# eclaire_sub_board.net
KiCad netlist of a schematic drawn in EAGLE
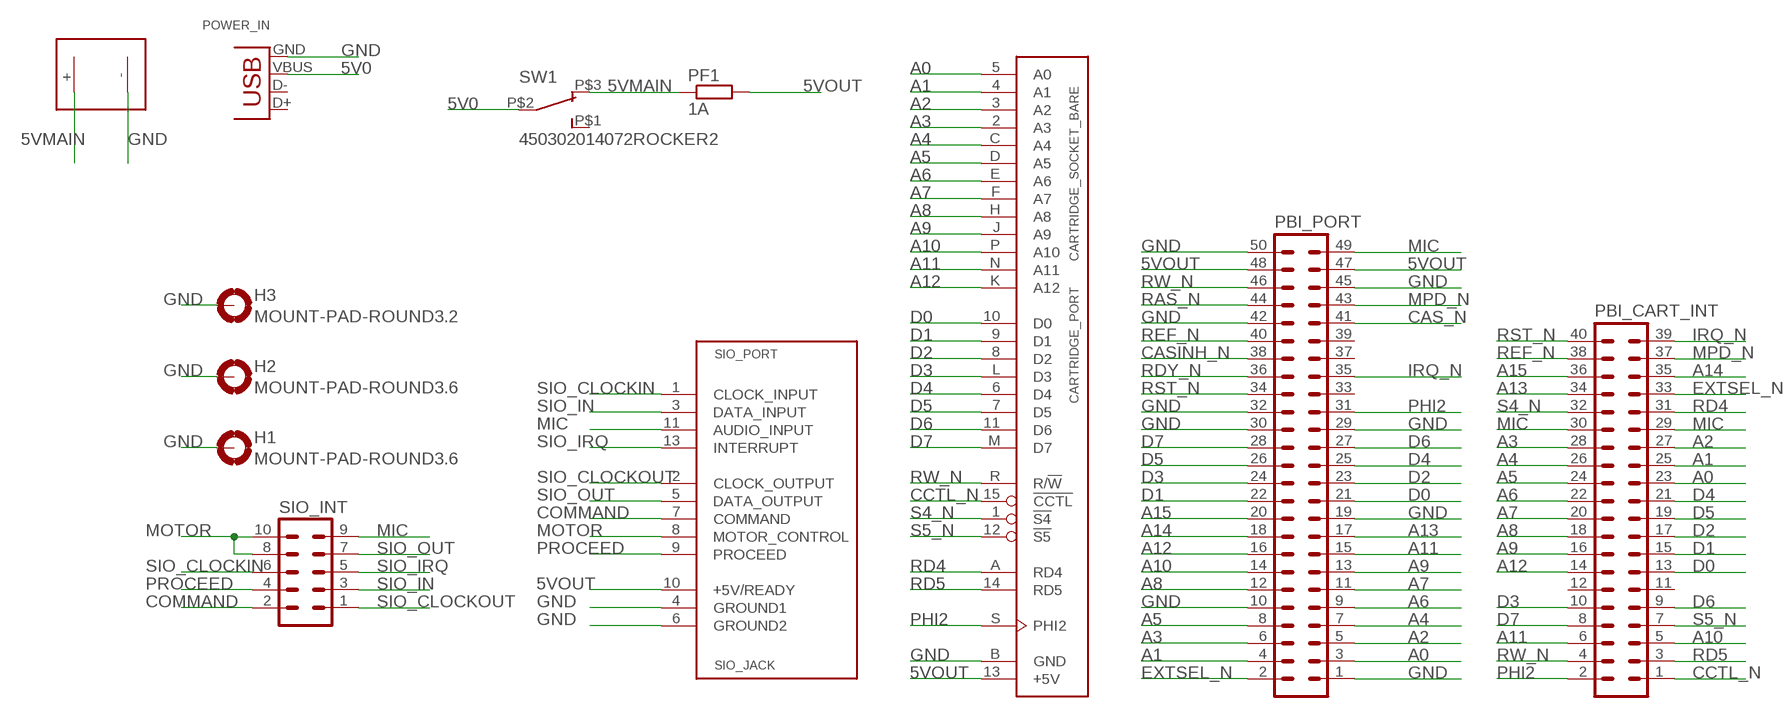
[diagram p0: schematic, sheet 1]

(export (version "E")
  (design (tool "Eeschema 10.0.6"))
  (components
    (comp (ref "CARTRIDGE_PORT")
      (value "CARTRIDGE_SOCKET_BARE")
      (footprint "eagle-import:CARTRIDGE_SOCKET")
      (libsource (lib "eagle-import") (part "CARTRIDGE_SOCKET_BARE"))
    )
    (comp (ref "H1")
      (value "MOUNT-PAD-ROUND3.6")
      (footprint "eagle-import:3,6-PAD")
      (libsource (lib "eagle-import") (part "MOUNT-PAD-ROUND3.6"))
    )
    (comp (ref "H2")
      (value "MOUNT-PAD-ROUND3.6")
      (footprint "eagle-import:3,6-PAD")
      (libsource (lib "eagle-import") (part "MOUNT-PAD-ROUND3.6"))
    )
    (comp (ref "H3")
      (value "MOUNT-PAD-ROUND3.2")
      (footprint "eagle-import:3,2-PAD")
      (libsource (lib "eagle-import") (part "MOUNT-PAD-ROUND3.2"))
    )
    (comp (ref "PBI_CART_INT")
      (value "ML40")
      (footprint "eagle-import:ML40")
      (libsource (lib "eagle-import") (part "ML40"))
    )
    (comp (ref "PBI_PORT")
      (value "ML50")
      (footprint "eagle-import:ML50")
      (libsource (lib "eagle-import") (part "ML50"))
    )
    (comp (ref "PF1")
      (value "1A")
      (footprint "eagle-import:R1206")
      (libsource (lib "eagle-import") (part "R-EU_R1206"))
    )
    (comp (ref "POWER_IN")
      (value "USB-B-H")
      (footprint "eagle-import:USB-B-H")
      (libsource (lib "eagle-import") (part "USB-B-H"))
    )
    (comp (ref "SIO_INT")
      (value "ML10")
      (footprint "eagle-import:ML10")
      (libsource (lib "eagle-import") (part "ML10"))
    )
    (comp (ref "SIO_PORT")
      (value "SIO_JACK")
      (footprint "eagle-import:SIO_JACK")
      (libsource (lib "eagle-import") (part "SIO_JACK"))
    )
    (comp (ref "SW1")
      (value "450302014072ROCKER2")
      (footprint "eagle-import:ROCKER_VERT_SPDT2")
      (libsource (lib "eagle-import") (part "450302014072ROCKER2"))
    )
    (comp (ref "U$6")
      (value "MOLEX_PS")
      (footprint "eagle-import:MOLEX_PS")
      (libsource (lib "eagle-import") (part "MOLEX_PS"))
    )
  )
  (nets
    (net (code "1") (name "/5V0") (class "Default")
      (node (ref "POWER_IN") (pin "VBUS") (pinfunction "VBUS_VBUS") (pintype "bidirectional"))
      (node (ref "SW1") (pin "P$2") (pinfunction "1_P$2") (pintype "passive"))
    )
    (net (code "2") (name "/5VMAIN") (class "Default")
      (node (ref "PF1") (pin "1") (pinfunction "1_1") (pintype "passive"))
      (node (ref "SW1") (pin "P$3") (pinfunction "3_P$3") (pintype "passive"))
      (node (ref "U$6") (pin "+") (pinfunction "+_+") (pintype "passive"))
    )
    (net (code "3") (name "/5VOUT") (class "Default")
      (node (ref "CARTRIDGE_PORT") (pin "13") (pinfunction "+5V_13") (pintype "power_in"))
      (node (ref "PBI_PORT") (pin "47") (pinfunction "47_47") (pintype "passive"))
      (node (ref "PBI_PORT") (pin "48") (pinfunction "48_48") (pintype "passive"))
      (node (ref "PF1") (pin "2") (pinfunction "2_2") (pintype "passive"))
      (node (ref "SIO_PORT") (pin "10") (pinfunction "+5V/READY_10") (pintype "power_in"))
    )
    (net (code "4") (name "/A0") (class "Default")
      (node (ref "CARTRIDGE_PORT") (pin "5") (pinfunction "A0_5") (pintype "input"))
      (node (ref "PBI_CART_INT") (pin "23") (pinfunction "23_23") (pintype "passive"))
      (node (ref "PBI_PORT") (pin "3") (pinfunction "3_3") (pintype "passive"))
    )
    (net (code "5") (name "/A1") (class "Default")
      (node (ref "CARTRIDGE_PORT") (pin "4") (pinfunction "A1_4") (pintype "input"))
      (node (ref "PBI_CART_INT") (pin "25") (pinfunction "25_25") (pintype "passive"))
      (node (ref "PBI_PORT") (pin "4") (pinfunction "4_4") (pintype "passive"))
    )
    (net (code "6") (name "/A2") (class "Default")
      (node (ref "CARTRIDGE_PORT") (pin "3") (pinfunction "A2_3") (pintype "input"))
      (node (ref "PBI_CART_INT") (pin "27") (pinfunction "27_27") (pintype "passive"))
      (node (ref "PBI_PORT") (pin "5") (pinfunction "5_5") (pintype "passive"))
    )
    (net (code "7") (name "/A3") (class "Default")
      (node (ref "CARTRIDGE_PORT") (pin "2") (pinfunction "A3_2") (pintype "input"))
      (node (ref "PBI_CART_INT") (pin "28") (pinfunction "28_28") (pintype "passive"))
      (node (ref "PBI_PORT") (pin "6") (pinfunction "6_6") (pintype "passive"))
    )
    (net (code "8") (name "/A4") (class "Default")
      (node (ref "CARTRIDGE_PORT") (pin "C") (pinfunction "A4_C") (pintype "input"))
      (node (ref "PBI_CART_INT") (pin "26") (pinfunction "26_26") (pintype "passive"))
      (node (ref "PBI_PORT") (pin "7") (pinfunction "7_7") (pintype "passive"))
    )
    (net (code "9") (name "/A5") (class "Default")
      (node (ref "CARTRIDGE_PORT") (pin "D") (pinfunction "A5_D") (pintype "input"))
      (node (ref "PBI_CART_INT") (pin "24") (pinfunction "24_24") (pintype "passive"))
      (node (ref "PBI_PORT") (pin "8") (pinfunction "8_8") (pintype "passive"))
    )
    (net (code "10") (name "/A6") (class "Default")
      (node (ref "CARTRIDGE_PORT") (pin "E") (pinfunction "A6_E") (pintype "input"))
      (node (ref "PBI_CART_INT") (pin "22") (pinfunction "22_22") (pintype "passive"))
      (node (ref "PBI_PORT") (pin "9") (pinfunction "9_9") (pintype "passive"))
    )
    (net (code "11") (name "/A7") (class "Default")
      (node (ref "CARTRIDGE_PORT") (pin "F") (pinfunction "A7_F") (pintype "input"))
      (node (ref "PBI_CART_INT") (pin "20") (pinfunction "20_20") (pintype "passive"))
      (node (ref "PBI_PORT") (pin "11") (pinfunction "11_11") (pintype "passive"))
    )
    (net (code "12") (name "/A8") (class "Default")
      (node (ref "CARTRIDGE_PORT") (pin "H") (pinfunction "A8_H") (pintype "input"))
      (node (ref "PBI_CART_INT") (pin "18") (pinfunction "18_18") (pintype "passive"))
      (node (ref "PBI_PORT") (pin "12") (pinfunction "12_12") (pintype "passive"))
    )
    (net (code "13") (name "/A9") (class "Default")
      (node (ref "CARTRIDGE_PORT") (pin "J") (pinfunction "A9_J") (pintype "input"))
      (node (ref "PBI_CART_INT") (pin "16") (pinfunction "16_16") (pintype "passive"))
      (node (ref "PBI_PORT") (pin "13") (pinfunction "13_13") (pintype "passive"))
    )
    (net (code "14") (name "/A10") (class "Default")
      (node (ref "CARTRIDGE_PORT") (pin "P") (pinfunction "A10_P") (pintype "input"))
      (node (ref "PBI_CART_INT") (pin "5") (pinfunction "5_5") (pintype "passive"))
      (node (ref "PBI_PORT") (pin "14") (pinfunction "14_14") (pintype "passive"))
    )
    (net (code "15") (name "/A11") (class "Default")
      (node (ref "CARTRIDGE_PORT") (pin "N") (pinfunction "A11_N") (pintype "input"))
      (node (ref "PBI_CART_INT") (pin "6") (pinfunction "6_6") (pintype "passive"))
      (node (ref "PBI_PORT") (pin "15") (pinfunction "15_15") (pintype "passive"))
    )
    (net (code "16") (name "/A12") (class "Default")
      (node (ref "CARTRIDGE_PORT") (pin "K") (pinfunction "A12_K") (pintype "input"))
      (node (ref "PBI_CART_INT") (pin "14") (pinfunction "14_14") (pintype "passive"))
      (node (ref "PBI_PORT") (pin "16") (pinfunction "16_16") (pintype "passive"))
    )
    (net (code "17") (name "/A13") (class "Default")
      (node (ref "PBI_CART_INT") (pin "34") (pinfunction "34_34") (pintype "passive"))
      (node (ref "PBI_PORT") (pin "17") (pinfunction "17_17") (pintype "passive"))
    )
    (net (code "18") (name "/A14") (class "Default")
      (node (ref "PBI_CART_INT") (pin "35") (pinfunction "35_35") (pintype "passive"))
      (node (ref "PBI_PORT") (pin "18") (pinfunction "18_18") (pintype "passive"))
    )
    (net (code "19") (name "/A15") (class "Default")
      (node (ref "PBI_CART_INT") (pin "36") (pinfunction "36_36") (pintype "passive"))
      (node (ref "PBI_PORT") (pin "20") (pinfunction "20_20") (pintype "passive"))
    )
    (net (code "20") (name "/CASINH_N") (class "Default")
      (node (ref "PBI_PORT") (pin "38") (pinfunction "38_38") (pintype "passive"))
    )
    (net (code "21") (name "/CAS_N") (class "Default")
      (node (ref "PBI_PORT") (pin "41") (pinfunction "41_41") (pintype "passive"))
    )
    (net (code "22") (name "/CCTL_N") (class "Default")
      (node (ref "CARTRIDGE_PORT") (pin "15") (pinfunction "~{CCTL}_15") (pintype "input"))
      (node (ref "PBI_CART_INT") (pin "1") (pinfunction "1_1") (pintype "passive"))
    )
    (net (code "23") (name "/COMMAND") (class "Default")
      (node (ref "SIO_INT") (pin "2") (pinfunction "2_2") (pintype "passive"))
      (node (ref "SIO_PORT") (pin "7") (pinfunction "COMMAND_7") (pintype "input"))
    )
    (net (code "24") (name "/D0") (class "Default")
      (node (ref "CARTRIDGE_PORT") (pin "10") (pinfunction "D0_10") (pintype "bidirectional"))
      (node (ref "PBI_CART_INT") (pin "13") (pinfunction "13_13") (pintype "passive"))
      (node (ref "PBI_PORT") (pin "21") (pinfunction "21_21") (pintype "passive"))
    )
    (net (code "25") (name "/D1") (class "Default")
      (node (ref "CARTRIDGE_PORT") (pin "9") (pinfunction "D1_9") (pintype "bidirectional"))
      (node (ref "PBI_CART_INT") (pin "15") (pinfunction "15_15") (pintype "passive"))
      (node (ref "PBI_PORT") (pin "22") (pinfunction "22_22") (pintype "passive"))
    )
    (net (code "26") (name "/D2") (class "Default")
      (node (ref "CARTRIDGE_PORT") (pin "8") (pinfunction "D2_8") (pintype "bidirectional"))
      (node (ref "PBI_CART_INT") (pin "17") (pinfunction "17_17") (pintype "passive"))
      (node (ref "PBI_PORT") (pin "23") (pinfunction "23_23") (pintype "passive"))
    )
    (net (code "27") (name "/D3") (class "Default")
      (node (ref "CARTRIDGE_PORT") (pin "L") (pinfunction "D3_L") (pintype "bidirectional"))
      (node (ref "PBI_CART_INT") (pin "10") (pinfunction "10_10") (pintype "passive"))
      (node (ref "PBI_PORT") (pin "24") (pinfunction "24_24") (pintype "passive"))
    )
    (net (code "28") (name "/D4") (class "Default")
      (node (ref "CARTRIDGE_PORT") (pin "6") (pinfunction "D4_6") (pintype "bidirectional"))
      (node (ref "PBI_CART_INT") (pin "21") (pinfunction "21_21") (pintype "passive"))
      (node (ref "PBI_PORT") (pin "25") (pinfunction "25_25") (pintype "passive"))
    )
    (net (code "29") (name "/D5") (class "Default")
      (node (ref "CARTRIDGE_PORT") (pin "7") (pinfunction "D5_7") (pintype "bidirectional"))
      (node (ref "PBI_CART_INT") (pin "19") (pinfunction "19_19") (pintype "passive"))
      (node (ref "PBI_PORT") (pin "26") (pinfunction "26_26") (pintype "passive"))
    )
    (net (code "30") (name "/D6") (class "Default")
      (node (ref "CARTRIDGE_PORT") (pin "11") (pinfunction "D6_11") (pintype "bidirectional"))
      (node (ref "PBI_CART_INT") (pin "9") (pinfunction "9_9") (pintype "passive"))
      (node (ref "PBI_PORT") (pin "27") (pinfunction "27_27") (pintype "passive"))
    )
    (net (code "31") (name "/D7") (class "Default")
      (node (ref "CARTRIDGE_PORT") (pin "M") (pinfunction "D7_M") (pintype "bidirectional"))
      (node (ref "PBI_CART_INT") (pin "8") (pinfunction "8_8") (pintype "passive"))
      (node (ref "PBI_PORT") (pin "28") (pinfunction "28_28") (pintype "passive"))
    )
    (net (code "32") (name "/EXTSEL_N") (class "Default")
      (node (ref "PBI_CART_INT") (pin "33") (pinfunction "33_33") (pintype "passive"))
      (node (ref "PBI_PORT") (pin "2") (pinfunction "2_2") (pintype "passive"))
    )
    (net (code "33") (name "/GND") (class "Default")
      (node (ref "CARTRIDGE_PORT") (pin "B") (pinfunction "GND_B") (pintype "power_in"))
      (node (ref "H1") (pin "B3,6") (pinfunction "MOUNT_B3,6") (pintype "passive"))
      (node (ref "H2") (pin "B3,6") (pinfunction "MOUNT_B3,6") (pintype "passive"))
      (node (ref "H3") (pin "B3,2") (pinfunction "MOUNT_B3,2") (pintype "passive"))
      (node (ref "PBI_PORT") (pin "1") (pinfunction "1_1") (pintype "passive"))
      (node (ref "PBI_PORT") (pin "10") (pinfunction "10_10") (pintype "passive"))
      (node (ref "PBI_PORT") (pin "19") (pinfunction "19_19") (pintype "passive"))
      (node (ref "PBI_PORT") (pin "29") (pinfunction "29_29") (pintype "passive"))
      (node (ref "PBI_PORT") (pin "30") (pinfunction "30_30") (pintype "passive"))
      (node (ref "PBI_PORT") (pin "32") (pinfunction "32_32") (pintype "passive"))
      (node (ref "PBI_PORT") (pin "42") (pinfunction "42_42") (pintype "passive"))
      (node (ref "PBI_PORT") (pin "45") (pinfunction "45_45") (pintype "passive"))
      (node (ref "PBI_PORT") (pin "50") (pinfunction "50_50") (pintype "passive"))
      (node (ref "POWER_IN") (pin "GND") (pinfunction "GND_GND") (pintype "bidirectional"))
      (node (ref "SIO_PORT") (pin "4") (pinfunction "GROUND1_4") (pintype "power_in"))
      (node (ref "SIO_PORT") (pin "6") (pinfunction "GROUND2_6") (pintype "power_in"))
      (node (ref "U$6") (pin "-") (pinfunction "--_-") (pintype "passive"))
    )
    (net (code "34") (name "/IRQ_N") (class "Default")
      (node (ref "PBI_CART_INT") (pin "39") (pinfunction "39_39") (pintype "passive"))
      (node (ref "PBI_PORT") (pin "35") (pinfunction "35_35") (pintype "passive"))
    )
    (net (code "35") (name "/MIC") (class "Default")
      (node (ref "PBI_CART_INT") (pin "29") (pinfunction "29_29") (pintype "passive"))
      (node (ref "PBI_CART_INT") (pin "30") (pinfunction "30_30") (pintype "passive"))
      (node (ref "PBI_PORT") (pin "49") (pinfunction "49_49") (pintype "passive"))
      (node (ref "SIO_INT") (pin "9") (pinfunction "9_9") (pintype "passive"))
      (node (ref "SIO_PORT") (pin "11") (pinfunction "AUDIO_INPUT_11") (pintype "output"))
    )
    (net (code "36") (name "/MOTOR") (class "Default")
      (node (ref "SIO_INT") (pin "10") (pinfunction "10_10") (pintype "passive"))
      (node (ref "SIO_INT") (pin "8") (pinfunction "8_8") (pintype "passive"))
      (node (ref "SIO_PORT") (pin "8") (pinfunction "MOTOR_CONTROL_8") (pintype "input"))
    )
    (net (code "37") (name "/MPD_N") (class "Default")
      (node (ref "PBI_CART_INT") (pin "37") (pinfunction "37_37") (pintype "passive"))
      (node (ref "PBI_PORT") (pin "43") (pinfunction "43_43") (pintype "passive"))
    )
    (net (code "38") (name "/PHI2") (class "Default")
      (node (ref "CARTRIDGE_PORT") (pin "S") (pinfunction "PHI2_S") (pintype "input"))
      (node (ref "PBI_CART_INT") (pin "2") (pinfunction "2_2") (pintype "passive"))
      (node (ref "PBI_PORT") (pin "31") (pinfunction "31_31") (pintype "passive"))
    )
    (net (code "39") (name "/PROCEED") (class "Default")
      (node (ref "SIO_INT") (pin "4") (pinfunction "4_4") (pintype "passive"))
      (node (ref "SIO_PORT") (pin "9") (pinfunction "PROCEED_9") (pintype "bidirectional"))
    )
    (net (code "40") (name "/RAS_N") (class "Default")
      (node (ref "PBI_PORT") (pin "44") (pinfunction "44_44") (pintype "passive"))
    )
    (net (code "41") (name "/RD4") (class "Default")
      (node (ref "CARTRIDGE_PORT") (pin "A") (pinfunction "RD4_A") (pintype "output"))
      (node (ref "PBI_CART_INT") (pin "31") (pinfunction "31_31") (pintype "passive"))
    )
    (net (code "42") (name "/RD5") (class "Default")
      (node (ref "CARTRIDGE_PORT") (pin "14") (pinfunction "RD5_14") (pintype "output"))
      (node (ref "PBI_CART_INT") (pin "3") (pinfunction "3_3") (pintype "passive"))
    )
    (net (code "43") (name "/RDY_N") (class "Default")
      (node (ref "PBI_PORT") (pin "36") (pinfunction "36_36") (pintype "passive"))
    )
    (net (code "44") (name "/REF_N") (class "Default")
      (node (ref "PBI_CART_INT") (pin "38") (pinfunction "38_38") (pintype "passive"))
      (node (ref "PBI_PORT") (pin "40") (pinfunction "40_40") (pintype "passive"))
    )
    (net (code "45") (name "/RST_N") (class "Default")
      (node (ref "PBI_CART_INT") (pin "40") (pinfunction "40_40") (pintype "passive"))
      (node (ref "PBI_PORT") (pin "34") (pinfunction "34_34") (pintype "passive"))
    )
    (net (code "46") (name "/RW_N") (class "Default")
      (node (ref "CARTRIDGE_PORT") (pin "R") (pinfunction "R/~{W}_R") (pintype "input"))
      (node (ref "PBI_CART_INT") (pin "4") (pinfunction "4_4") (pintype "passive"))
      (node (ref "PBI_PORT") (pin "46") (pinfunction "46_46") (pintype "passive"))
    )
    (net (code "47") (name "/S4_N") (class "Default")
      (node (ref "CARTRIDGE_PORT") (pin "1") (pinfunction "~{S4}_1") (pintype "input"))
      (node (ref "PBI_CART_INT") (pin "32") (pinfunction "32_32") (pintype "passive"))
    )
    (net (code "48") (name "/S5_N") (class "Default")
      (node (ref "CARTRIDGE_PORT") (pin "12") (pinfunction "~{S5}_12") (pintype "input"))
      (node (ref "PBI_CART_INT") (pin "7") (pinfunction "7_7") (pintype "passive"))
    )
    (net (code "49") (name "/SIO_CLOCKIN") (class "Default")
      (node (ref "SIO_INT") (pin "6") (pinfunction "6_6") (pintype "passive"))
      (node (ref "SIO_PORT") (pin "1") (pinfunction "CLOCK_INPUT_1") (pintype "output"))
    )
    (net (code "50") (name "/SIO_CLOCKOUT") (class "Default")
      (node (ref "SIO_INT") (pin "1") (pinfunction "1_1") (pintype "passive"))
      (node (ref "SIO_PORT") (pin "2") (pinfunction "CLOCK_OUTPUT_2") (pintype "input"))
    )
    (net (code "51") (name "/SIO_IN") (class "Default")
      (node (ref "SIO_INT") (pin "3") (pinfunction "3_3") (pintype "passive"))
      (node (ref "SIO_PORT") (pin "3") (pinfunction "DATA_INPUT_3") (pintype "output"))
    )
    (net (code "52") (name "/SIO_IRQ") (class "Default")
      (node (ref "SIO_INT") (pin "5") (pinfunction "5_5") (pintype "passive"))
      (node (ref "SIO_PORT") (pin "13") (pinfunction "INTERRUPT_13") (pintype "output"))
    )
    (net (code "53") (name "/SIO_OUT") (class "Default")
      (node (ref "SIO_INT") (pin "7") (pinfunction "7_7") (pintype "passive"))
      (node (ref "SIO_PORT") (pin "5") (pinfunction "DATA_OUTPUT_5") (pintype "input"))
    )
    (net (code "54") (name "unconnected-(PBI_CART_INT-Pad11)") (class "Default")
      (node (ref "PBI_CART_INT") (pin "11") (pinfunction "11_11") (pintype "passive"))
    )
    (net (code "55") (name "unconnected-(PBI_CART_INT-Pad12)") (class "Default")
      (node (ref "PBI_CART_INT") (pin "12") (pinfunction "12_12") (pintype "passive"))
    )
    (net (code "56") (name "unconnected-(PBI_PORT-Pad33)") (class "Default")
      (node (ref "PBI_PORT") (pin "33") (pinfunction "33_33") (pintype "passive"))
    )
    (net (code "57") (name "unconnected-(PBI_PORT-Pad37)") (class "Default")
      (node (ref "PBI_PORT") (pin "37") (pinfunction "37_37") (pintype "passive"))
    )
    (net (code "58") (name "unconnected-(PBI_PORT-Pad39)") (class "Default")
      (node (ref "PBI_PORT") (pin "39") (pinfunction "39_39") (pintype "passive"))
    )
    (net (code "59") (name "unconnected-(POWER_IN-PadD+)") (class "Default")
      (node (ref "POWER_IN") (pin "D+") (pinfunction "D+_D+") (pintype "bidirectional"))
    )
    (net (code "60") (name "unconnected-(POWER_IN-PadD-)") (class "Default")
      (node (ref "POWER_IN") (pin "D-") (pinfunction "D-_D-") (pintype "bidirectional"))
    )
    (net (code "61") (name "unconnected-(SW1-2-PadP$1)") (class "Default")
      (node (ref "SW1") (pin "P$1") (pinfunction "2_P$1") (pintype "passive"))
    )
  )
)
